# Pi1541_Rot.net
KiCad netlist of a schematic drawn in EAGLE
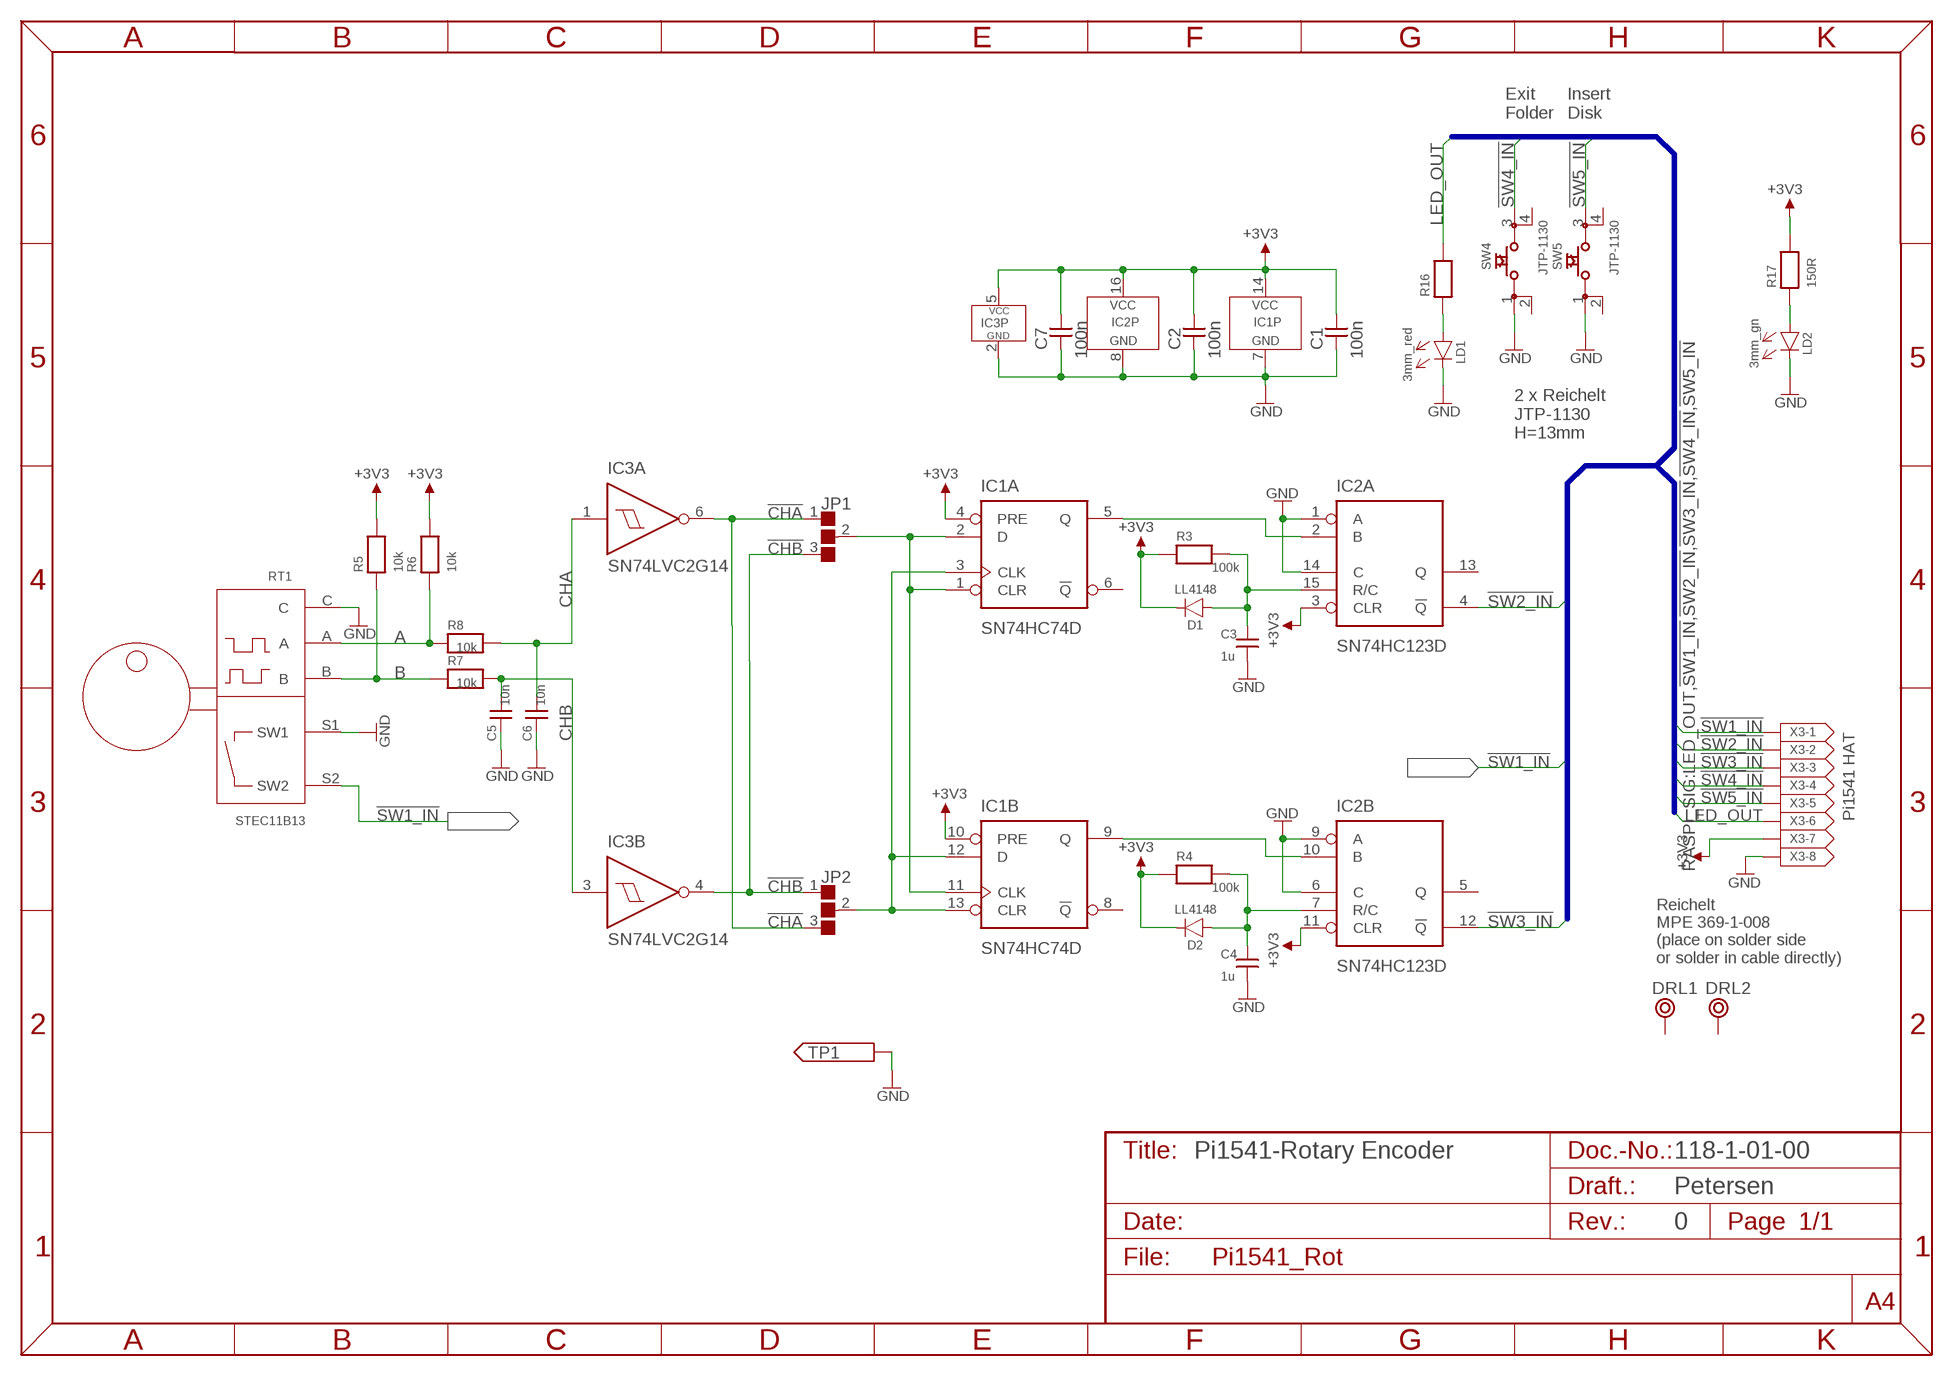
[diagram p0: schematic, sheet 1]

(export (version "E")
  (design (tool "Eeschema 10.0.6"))
  (components
    (comp (ref "C1")
      (value "100n")
      (footprint "eagle-import:0805")
      (libsource (lib "eagle-import") (part "C-0805"))
    )
    (comp (ref "C2")
      (value "100n")
      (footprint "eagle-import:0805")
      (libsource (lib "eagle-import") (part "C-0805"))
    )
    (comp (ref "C3")
      (value "1u")
      (footprint "eagle-import:0805")
      (libsource (lib "eagle-import") (part "C-0805"))
    )
    (comp (ref "C4")
      (value "1u")
      (footprint "eagle-import:0805")
      (libsource (lib "eagle-import") (part "C-0805"))
    )
    (comp (ref "C5")
      (value "10n")
      (footprint "eagle-import:0805")
      (libsource (lib "eagle-import") (part "C-0805"))
    )
    (comp (ref "C6")
      (value "10n")
      (footprint "eagle-import:0805")
      (libsource (lib "eagle-import") (part "C-0805"))
    )
    (comp (ref "C7")
      (value "100n")
      (footprint "eagle-import:0805")
      (libsource (lib "eagle-import") (part "C-0805"))
    )
    (comp (ref "D1")
      (value "LL4148")
      (footprint "eagle-import:SOD80C")
      (libsource (lib "eagle-import") (part "LL4148"))
    )
    (comp (ref "D2")
      (value "LL4148")
      (footprint "eagle-import:SOD80C")
      (libsource (lib "eagle-import") (part "LL4148"))
    )
    (comp (ref "DRL1")
      (value "BOHR2,8")
      (footprint "eagle-import:BOHR2,8_")
      (libsource (lib "eagle-import") (part "BOHR2,8"))
    )
    (comp (ref "DRL2")
      (value "BOHR2,8")
      (footprint "eagle-import:BOHR2,8_")
      (libsource (lib "eagle-import") (part "BOHR2,8"))
    )
    (comp (ref "IC1")
      (value "SN74HC74D")
      (footprint "eagle-import:SO-14")
      (libsource (lib "eagle-import") (part "7474HC"))
    )
    (comp (ref "IC2")
      (value "SN74HC123D")
      (footprint "eagle-import:SO-16")
      (libsource (lib "eagle-import") (part "74123"))
    )
    (comp (ref "IC3")
      (value "SN74LVC2G14")
      (footprint "eagle-import:SOT23-6")
      (libsource (lib "eagle-import") (part "SN74LVC2G14"))
    )
    (comp (ref "JP1")
      (value "JMP_0603")
      (footprint "eagle-import:CP3P")
      (libsource (lib "eagle-import") (part "JMP_0603"))
    )
    (comp (ref "JP2")
      (value "JMP_0603")
      (footprint "eagle-import:CP3P")
      (libsource (lib "eagle-import") (part "JMP_0603"))
    )
    (comp (ref "LD1")
      (value "3mm_red")
      (footprint "eagle-import:3MM")
      (libsource (lib "eagle-import") (part "3MM"))
    )
    (comp (ref "LD2")
      (value "3mm_gn")
      (footprint "eagle-import:3MM")
      (libsource (lib "eagle-import") (part "3MM"))
    )
    (comp (ref "R3")
      (value "100k")
      (footprint "eagle-import:0805")
      (libsource (lib "eagle-import") (part "R-0805"))
    )
    (comp (ref "R4")
      (value "100k")
      (footprint "eagle-import:0805")
      (libsource (lib "eagle-import") (part "R-0805"))
    )
    (comp (ref "R5")
      (value "10k")
      (footprint "eagle-import:0805")
      (libsource (lib "eagle-import") (part "R-0805"))
    )
    (comp (ref "R6")
      (value "10k")
      (footprint "eagle-import:0805")
      (libsource (lib "eagle-import") (part "R-0805"))
    )
    (comp (ref "R7")
      (value "10k")
      (footprint "eagle-import:0805")
      (libsource (lib "eagle-import") (part "R-0805"))
    )
    (comp (ref "R8")
      (value "10k")
      (footprint "eagle-import:0805")
      (libsource (lib "eagle-import") (part "R-0805"))
    )
    (comp (ref "R16")
      (value "150R")
      (footprint "eagle-import:0805")
      (libsource (lib "eagle-import") (part "R-0805"))
    )
    (comp (ref "R17")
      (value "150R")
      (footprint "eagle-import:0805")
      (libsource (lib "eagle-import") (part "R-0805"))
    )
    (comp (ref "RT1")
      (value "STEC11B13")
      (footprint "eagle-import:STEC11B13")
      (libsource (lib "eagle-import") (part "STEC11B13"))
    )
    (comp (ref "SW4")
      (value "JTP-1130")
      (footprint "eagle-import:JTP-1130")
      (libsource (lib "eagle-import") (part "JTP-1130"))
    )
    (comp (ref "SW5")
      (value "JTP-1130")
      (footprint "eagle-import:JTP-1130")
      (libsource (lib "eagle-import") (part "JTP-1130"))
    )
    (comp (ref "TP1")
      (value "PAD1,0/AUTO")
      (footprint "eagle-import:1.0_AUTO")
      (libsource (lib "eagle-import") (part "PAD1,0/AUTO"))
    )
    (comp (ref "X3")
      (value "MICMA08B")
      (footprint "eagle-import:MICMA08B")
      (libsource (lib "eagle-import") (part "MICMA08B"))
    )
  )
  (nets
    (net (code "2") (name "+3V3") (class "Default")
      (node (ref "C1") (pin "2") (pinfunction "2_2") (pintype "passive"))
      (node (ref "C2") (pin "2") (pinfunction "2_2") (pintype "passive"))
      (node (ref "C7") (pin "2") (pinfunction "2_2") (pintype "passive"))
      (node (ref "D1") (pin "K") (pinfunction "K_K") (pintype "passive"))
      (node (ref "D2") (pin "K") (pinfunction "K_K") (pintype "passive"))
      (node (ref "IC1") (pin "10") (pinfunction "PRE_10") (pintype "input"))
      (node (ref "IC1") (pin "14") (pinfunction "VCC_14") (pintype "bidirectional"))
      (node (ref "IC1") (pin "4") (pinfunction "PRE_4") (pintype "input"))
      (node (ref "IC2") (pin "11") (pinfunction "CLR_11") (pintype "input"))
      (node (ref "IC2") (pin "16") (pinfunction "VCC_16") (pintype "bidirectional"))
      (node (ref "IC2") (pin "3") (pinfunction "CLR_3") (pintype "input"))
      (node (ref "IC3") (pin "5") (pinfunction "VCC_5") (pintype "power_in"))
      (node (ref "R17") (pin "2") (pinfunction "2_2") (pintype "passive"))
      (node (ref "R3") (pin "1") (pinfunction "1_1") (pintype "passive"))
      (node (ref "R4") (pin "1") (pinfunction "1_1") (pintype "passive"))
      (node (ref "R5") (pin "2") (pinfunction "2_2") (pintype "passive"))
      (node (ref "R6") (pin "2") (pinfunction "2_2") (pintype "passive"))
      (node (ref "X3") (pin "7") (pinfunction "1_7") (pintype "bidirectional"))
    )
    (net (code "3") (name "/A") (class "Default")
      (node (ref "R6") (pin "1") (pinfunction "1_1") (pintype "passive"))
      (node (ref "R8") (pin "1") (pinfunction "1_1") (pintype "passive"))
      (node (ref "RT1") (pin "A") (pinfunction "A_A") (pintype "passive"))
    )
    (net (code "4") (name "/B") (class "Default")
      (node (ref "R5") (pin "1") (pinfunction "1_1") (pintype "passive"))
      (node (ref "R7") (pin "1") (pinfunction "1_1") (pintype "passive"))
      (node (ref "RT1") (pin "B") (pinfunction "B_B") (pintype "passive"))
    )
    (net (code "5") (name "/CHA") (class "Default")
      (node (ref "C6") (pin "2") (pinfunction "2_2") (pintype "passive"))
      (node (ref "IC3") (pin "1") (pinfunction "I_1") (pintype "input"))
      (node (ref "R8") (pin "2") (pinfunction "2_2") (pintype "passive"))
    )
    (net (code "6") (name "/CHB") (class "Default")
      (node (ref "C5") (pin "2") (pinfunction "2_2") (pintype "passive"))
      (node (ref "IC3") (pin "3") (pinfunction "I_3") (pintype "input"))
      (node (ref "R7") (pin "2") (pinfunction "2_2") (pintype "passive"))
    )
    (net (code "7") (name "/LED_OUT") (class "Default")
      (node (ref "R16") (pin "2") (pinfunction "2_2") (pintype "passive"))
      (node (ref "X3") (pin "6") (pinfunction "1_6") (pintype "bidirectional"))
    )
    (net (code "9") (name "/~{CHA}") (class "Default")
      (node (ref "IC3") (pin "6") (pinfunction "O_6") (pintype "output"))
      (node (ref "JP1") (pin "1") (pinfunction "1_1") (pintype "bidirectional"))
      (node (ref "JP2") (pin "3") (pinfunction "3_3") (pintype "bidirectional"))
    )
    (net (code "10") (name "/~{CHB}") (class "Default")
      (node (ref "IC3") (pin "4") (pinfunction "O_4") (pintype "output"))
      (node (ref "JP1") (pin "3") (pinfunction "3_3") (pintype "bidirectional"))
      (node (ref "JP2") (pin "1") (pinfunction "1_1") (pintype "bidirectional"))
    )
    (net (code "11") (name "/~{SW1_IN}") (class "Default")
      (node (ref "RT1") (pin "S2") (pinfunction "SW2_S2") (pintype "passive"))
      (node (ref "X3") (pin "1") (pinfunction "1_1") (pintype "bidirectional"))
    )
    (net (code "12") (name "/~{SW2_IN}") (class "Default")
      (node (ref "IC2") (pin "4") (pinfunction "~{Q}_4") (pintype "output"))
      (node (ref "X3") (pin "2") (pinfunction "1_2") (pintype "bidirectional"))
    )
    (net (code "13") (name "/~{SW3_IN}") (class "Default")
      (node (ref "IC2") (pin "12") (pinfunction "~{Q}_12") (pintype "output"))
      (node (ref "X3") (pin "3") (pinfunction "1_3") (pintype "bidirectional"))
    )
    (net (code "14") (name "/~{SW4_IN}") (class "Default")
      (node (ref "SW4") (pin "3") (pinfunction "3_3") (pintype "passive"))
      (node (ref "X3") (pin "4") (pinfunction "1_4") (pintype "bidirectional"))
    )
    (net (code "15") (name "/~{SW5_IN}") (class "Default")
      (node (ref "SW5") (pin "3") (pinfunction "3_3") (pintype "passive"))
      (node (ref "X3") (pin "5") (pinfunction "1_5") (pintype "bidirectional"))
    )
    (net (code "16") (name "GND") (class "Default")
      (node (ref "C1") (pin "1") (pinfunction "1_1") (pintype "passive"))
      (node (ref "C2") (pin "1") (pinfunction "1_1") (pintype "passive"))
      (node (ref "C3") (pin "2") (pinfunction "2_2") (pintype "passive"))
      (node (ref "C4") (pin "2") (pinfunction "2_2") (pintype "passive"))
      (node (ref "C5") (pin "1") (pinfunction "1_1") (pintype "passive"))
      (node (ref "C6") (pin "1") (pinfunction "1_1") (pintype "passive"))
      (node (ref "C7") (pin "1") (pinfunction "1_1") (pintype "passive"))
      (node (ref "IC1") (pin "7") (pinfunction "GND_7") (pintype "bidirectional"))
      (node (ref "IC2") (pin "1") (pinfunction "A_1") (pintype "input"))
      (node (ref "IC2") (pin "14") (pinfunction "C_14") (pintype "input"))
      (node (ref "IC2") (pin "6") (pinfunction "C_6") (pintype "input"))
      (node (ref "IC2") (pin "8") (pinfunction "GND_8") (pintype "bidirectional"))
      (node (ref "IC2") (pin "9") (pinfunction "A_9") (pintype "input"))
      (node (ref "IC3") (pin "2") (pinfunction "GND_2") (pintype "power_in"))
      (node (ref "LD1") (pin "C") (pinfunction "K_C") (pintype "bidirectional"))
      (node (ref "LD2") (pin "C") (pinfunction "K_C") (pintype "bidirectional"))
      (node (ref "RT1") (pin "C") (pinfunction "C_C") (pintype "passive"))
      (node (ref "RT1") (pin "S1") (pinfunction "SW1_S1") (pintype "passive"))
      (node (ref "SW4") (pin "1") (pinfunction "1_1") (pintype "passive"))
      (node (ref "SW5") (pin "1") (pinfunction "1_1") (pintype "passive"))
      (node (ref "TP1") (pin "1") (pinfunction "1_1") (pintype "passive"))
      (node (ref "X3") (pin "8") (pinfunction "1_8") (pintype "bidirectional"))
    )
    (net (code "17") (name "Net-(IC1A-CLK)") (class "Default")
      (node (ref "IC1") (pin "12") (pinfunction "D_12") (pintype "input"))
      (node (ref "IC1") (pin "13") (pinfunction "CLR_13") (pintype "input"))
      (node (ref "IC1") (pin "3") (pinfunction "CLK_3") (pintype "input"))
      (node (ref "JP2") (pin "2") (pinfunction "2_2") (pintype "bidirectional"))
    )
    (net (code "18") (name "Net-(IC1A-CLR)") (class "Default")
      (node (ref "IC1") (pin "1") (pinfunction "CLR_1") (pintype "input"))
      (node (ref "IC1") (pin "11") (pinfunction "CLK_11") (pintype "input"))
      (node (ref "IC1") (pin "2") (pinfunction "D_2") (pintype "input"))
      (node (ref "JP1") (pin "2") (pinfunction "2_2") (pintype "bidirectional"))
    )
    (net (code "19") (name "Net-(IC1A-Q)") (class "Default")
      (node (ref "IC1") (pin "5") (pinfunction "Q_5") (pintype "output"))
      (node (ref "IC2") (pin "2") (pinfunction "B_2") (pintype "input"))
    )
    (net (code "20") (name "Net-(IC1B-Q)") (class "Default")
      (node (ref "IC1") (pin "9") (pinfunction "Q_9") (pintype "output"))
      (node (ref "IC2") (pin "10") (pinfunction "B_10") (pintype "input"))
    )
    (net (code "21") (name "Net-(IC2A-R{slash}C)") (class "Default")
      (node (ref "C3") (pin "1") (pinfunction "1_1") (pintype "passive"))
      (node (ref "D1") (pin "A") (pinfunction "A_A") (pintype "passive"))
      (node (ref "IC2") (pin "15") (pinfunction "R/C_15") (pintype "input"))
      (node (ref "R3") (pin "2") (pinfunction "2_2") (pintype "passive"))
    )
    (net (code "22") (name "Net-(IC2B-R{slash}C)") (class "Default")
      (node (ref "C4") (pin "1") (pinfunction "1_1") (pintype "passive"))
      (node (ref "D2") (pin "A") (pinfunction "A_A") (pintype "passive"))
      (node (ref "IC2") (pin "7") (pinfunction "R/C_7") (pintype "input"))
      (node (ref "R4") (pin "2") (pinfunction "2_2") (pintype "passive"))
    )
    (net (code "23") (name "Net-(LD1-PadA)") (class "Default")
      (node (ref "LD1") (pin "A") (pinfunction "A_A") (pintype "bidirectional"))
      (node (ref "R16") (pin "1") (pinfunction "1_1") (pintype "passive"))
    )
    (net (code "24") (name "Net-(LD2-PadA)") (class "Default")
      (node (ref "LD2") (pin "A") (pinfunction "A_A") (pintype "bidirectional"))
      (node (ref "R17") (pin "1") (pinfunction "1_1") (pintype "passive"))
    )
    (net (code "25") (name "unconnected-(DRL1-P$1-PadMH)") (class "Default")
      (node (ref "DRL1") (pin "MH") (pinfunction "P$1_MH") (pintype "passive"))
    )
    (net (code "26") (name "unconnected-(DRL2-P$1-PadMH)") (class "Default")
      (node (ref "DRL2") (pin "MH") (pinfunction "P$1_MH") (pintype "passive"))
    )
    (net (code "27") (name "unconnected-(IC1A-~{Q}-Pad6)") (class "Default")
      (node (ref "IC1") (pin "6") (pinfunction "~{Q}_6") (pintype "output"))
    )
    (net (code "28") (name "unconnected-(IC1B-~{Q}-Pad8)") (class "Default")
      (node (ref "IC1") (pin "8") (pinfunction "~{Q}_8") (pintype "output"))
    )
    (net (code "29") (name "unconnected-(IC2A-Q-Pad13)") (class "Default")
      (node (ref "IC2") (pin "13") (pinfunction "Q_13") (pintype "output"))
    )
    (net (code "30") (name "unconnected-(IC2B-Q-Pad5)") (class "Default")
      (node (ref "IC2") (pin "5") (pinfunction "Q_5") (pintype "output"))
    )
    (net (code "31") (name "unconnected-(SW4-Pad2)") (class "Default")
      (node (ref "SW4") (pin "2") (pinfunction "2_2") (pintype "passive"))
    )
    (net (code "32") (name "unconnected-(SW4-Pad4)") (class "Default")
      (node (ref "SW4") (pin "4") (pinfunction "4_4") (pintype "passive"))
    )
    (net (code "33") (name "unconnected-(SW5-Pad2)") (class "Default")
      (node (ref "SW5") (pin "2") (pinfunction "2_2") (pintype "passive"))
    )
    (net (code "34") (name "unconnected-(SW5-Pad4)") (class "Default")
      (node (ref "SW5") (pin "4") (pinfunction "4_4") (pintype "passive"))
    )
  )
)
